# Occulow-Control.net
KiCad netlist of a schematic drawn in EAGLE
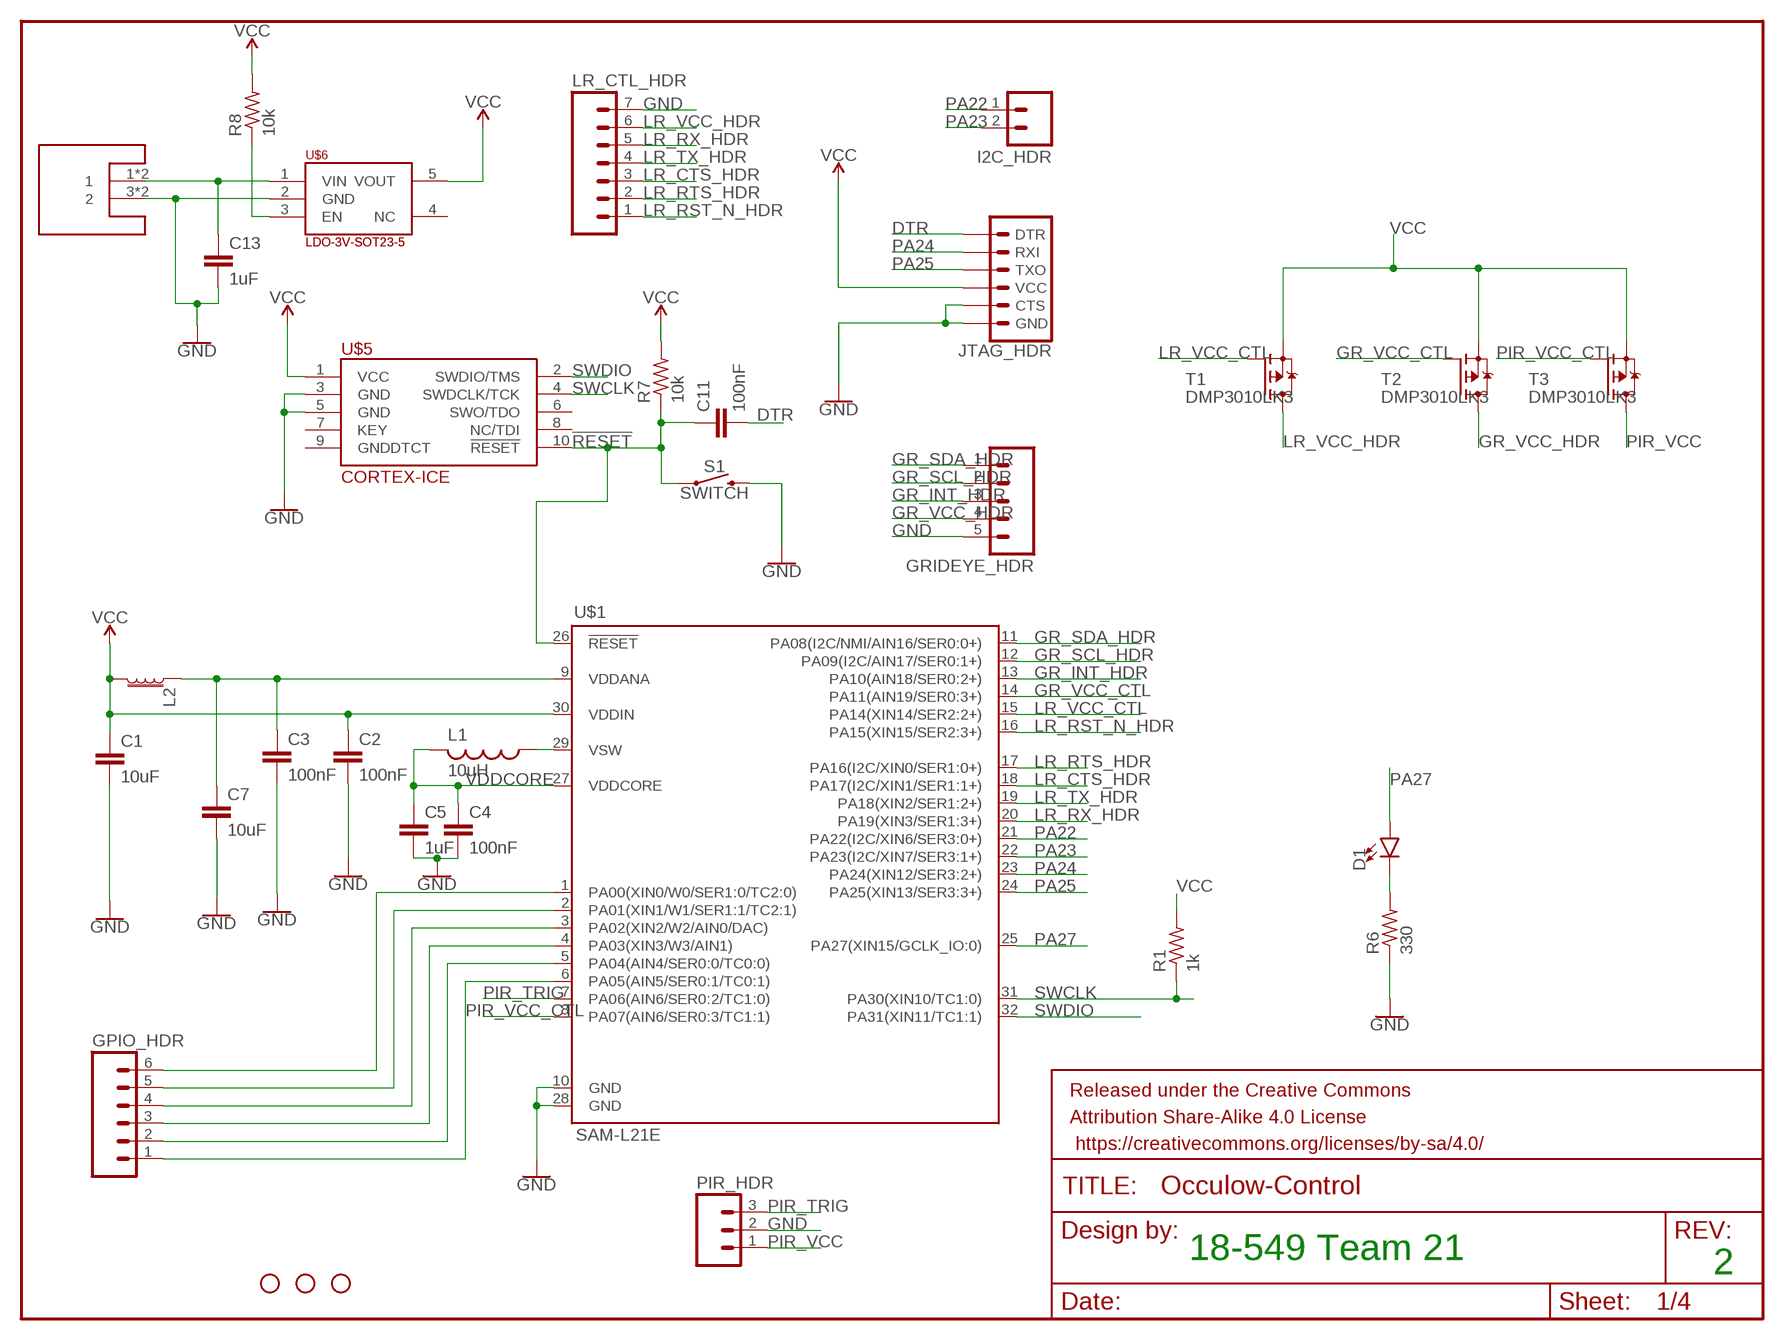
[diagram p0: schematic, sheet 1]
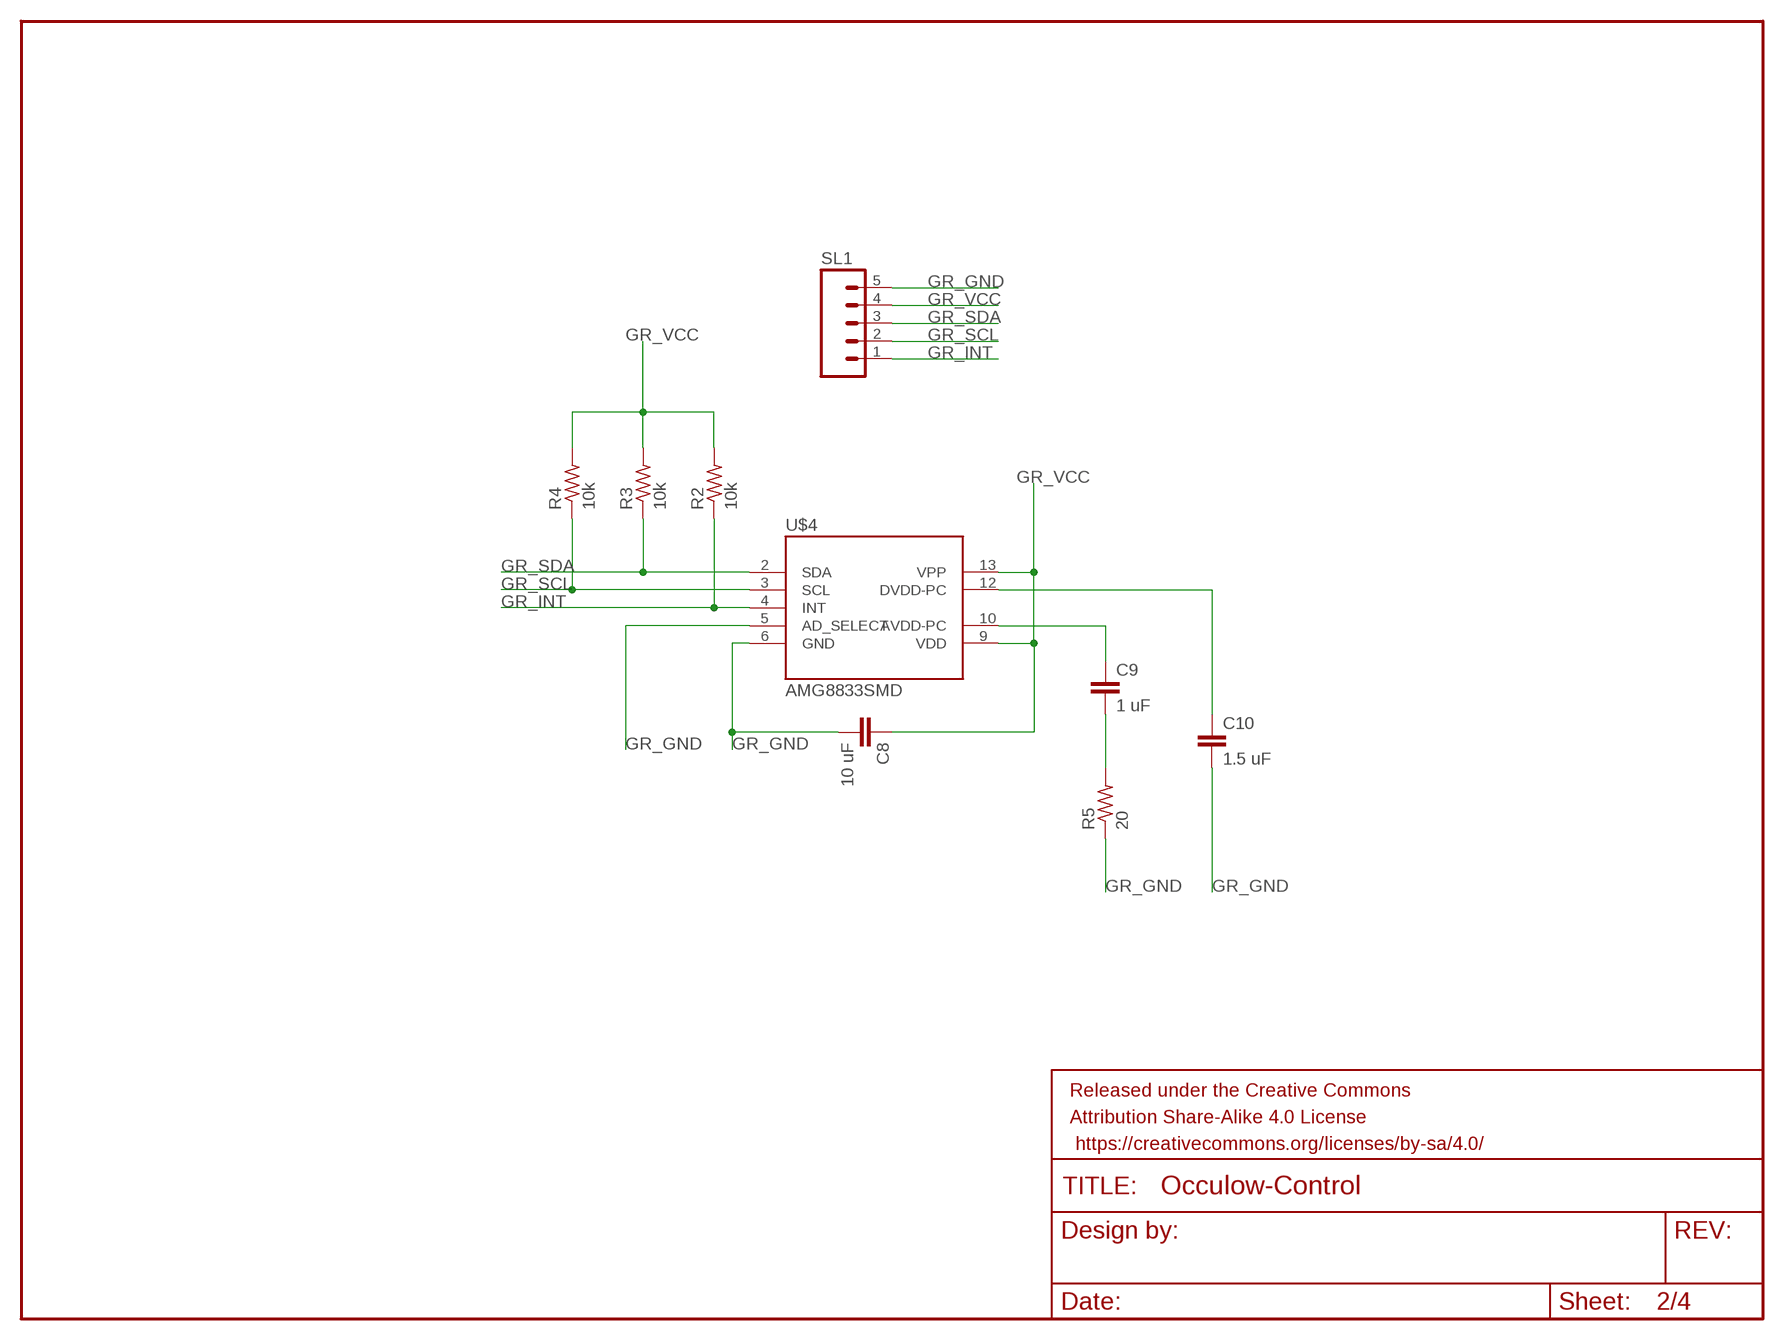
[diagram p1: schematic, sheet 2]
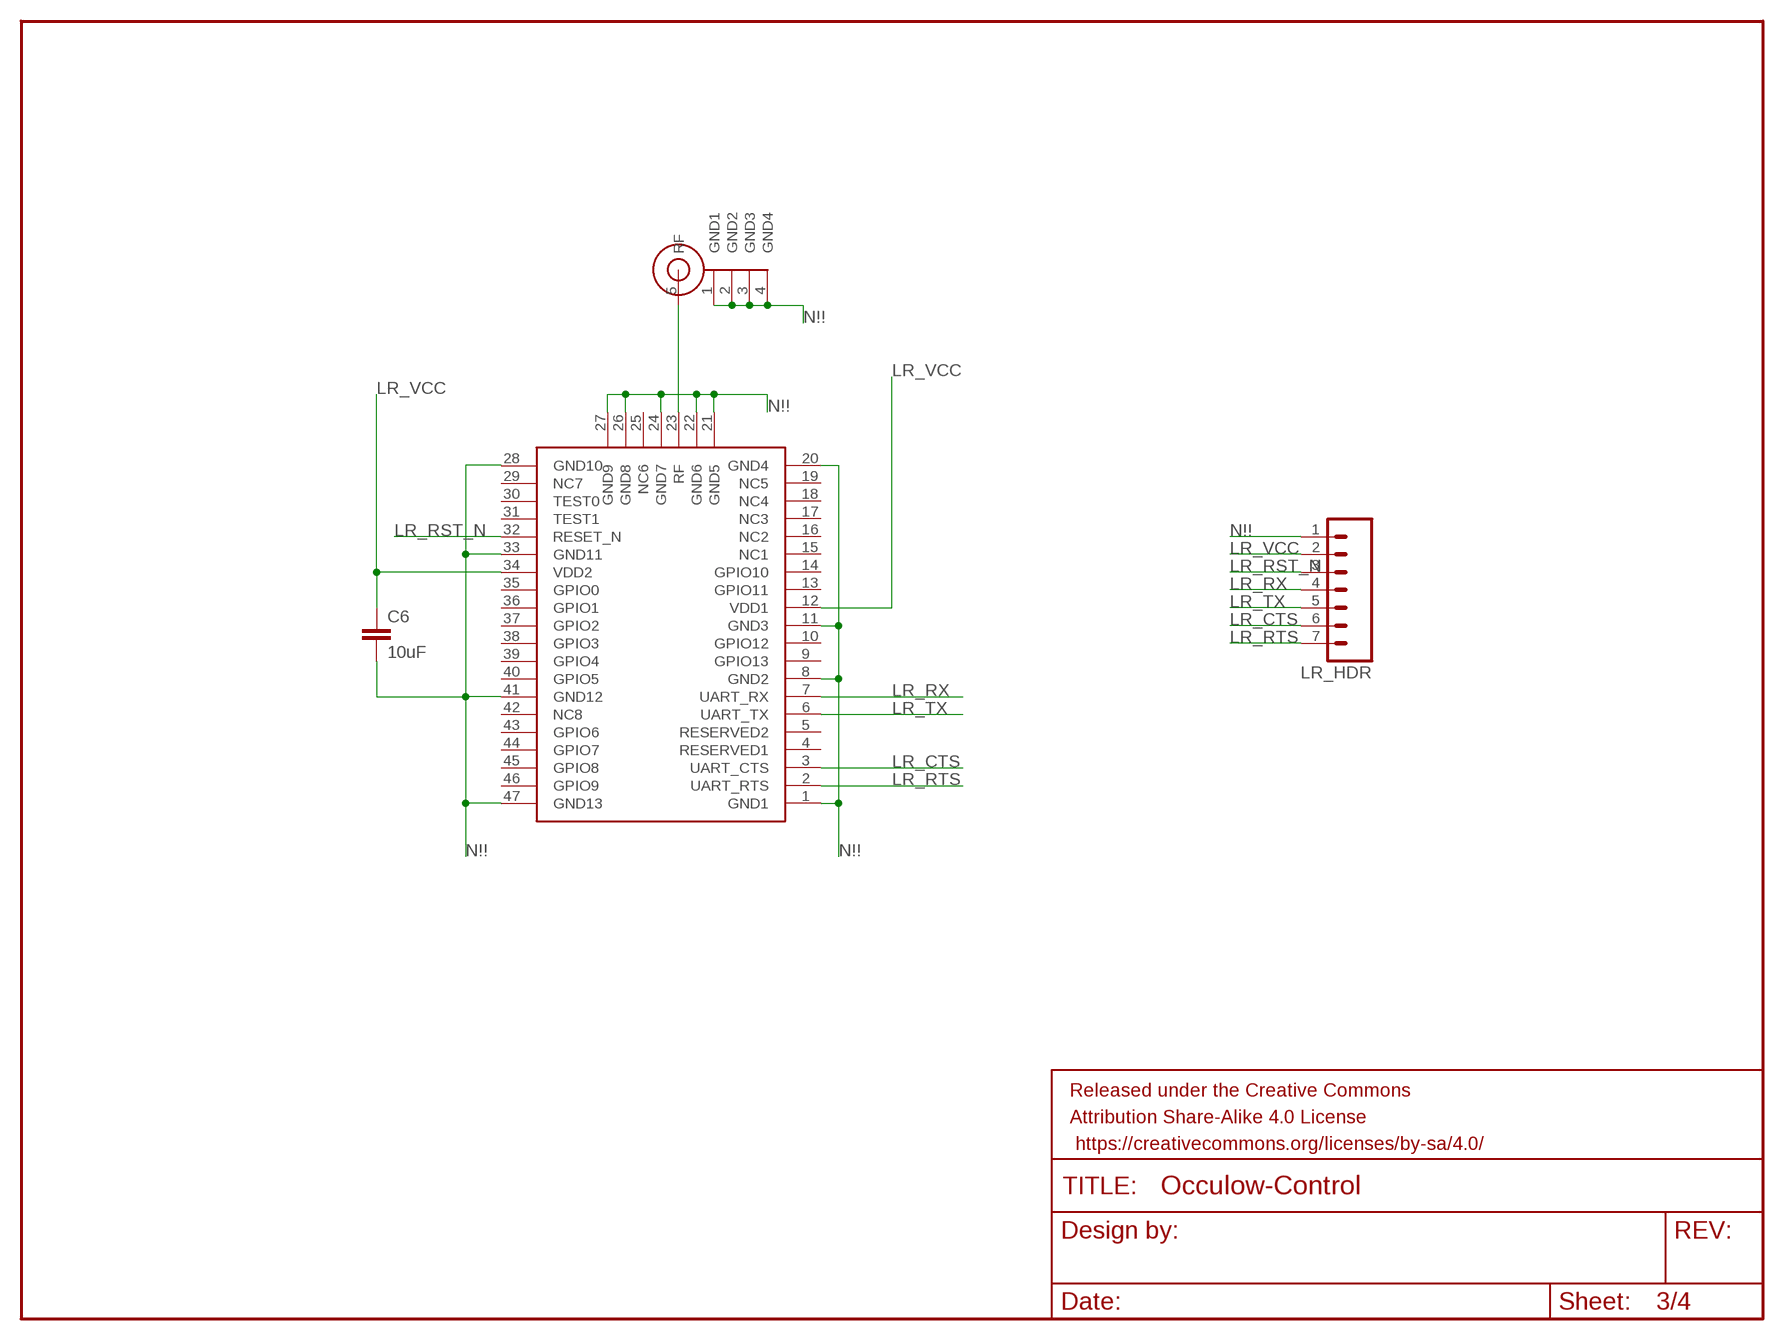
[diagram p2: schematic, sheet 3]

(export (version "E")
  (design (tool "Eeschema 10.0.6"))
  (components
    (comp (ref "C8")
      (value "10 uF")
      (footprint "eagle-import:C1206")
      (libsource (lib "eagle-import") (part "C-EUC1206"))
    )
    (comp (ref "C9")
      (value "1 uF")
      (footprint "eagle-import:C1206")
      (libsource (lib "eagle-import") (part "C-EUC1206"))
    )
    (comp (ref "C10")
      (value "1.5 uF")
      (footprint "eagle-import:C1206")
      (libsource (lib "eagle-import") (part "C-EUC1206"))
    )
    (comp (ref "FRAME2")
      (value "FRAME-LETTERNO_PACKAGE")
      (footprint "eagle-import:DUMMY")
      (fields (field (name "DESIGNER") "Nobody"))
      (libsource (lib "eagle-import") (part "FRAME-LETTERNO_PACKAGE"))
    )
    (comp (ref "R2")
      (value "10k")
      (footprint "eagle-import:R1206")
      (libsource (lib "eagle-import") (part "R-US_R1206"))
    )
    (comp (ref "R3")
      (value "10k")
      (footprint "eagle-import:R1206")
      (libsource (lib "eagle-import") (part "R-US_R1206"))
    )
    (comp (ref "R4")
      (value "10k")
      (footprint "eagle-import:R1206")
      (libsource (lib "eagle-import") (part "R-US_R1206"))
    )
    (comp (ref "R5")
      (value "20")
      (footprint "eagle-import:R1206")
      (libsource (lib "eagle-import") (part "R-US_R1206"))
    )
    (comp (ref "SL1")
      (value "M05")
      (footprint "eagle-import:05P")
      (libsource (lib "eagle-import") (part "M05"))
    )
    (comp (ref "U$4")
      (value "AMG8833SMD")
      (footprint "eagle-import:AMG8833")
      (libsource (lib "eagle-import") (part "AMG8833SMD"))
    )
    (comp (ref "C6")
      (value "10uF")
      (footprint "eagle-import:C1206")
      (libsource (lib "eagle-import") (part "C-EUC1206"))
    )
    (comp (ref "FRAME3")
      (value "FRAME-LETTERNO_PACKAGE")
      (footprint "eagle-import:DUMMY")
      (fields (field (name "DESIGNER") "Nobody"))
      (libsource (lib "eagle-import") (part "FRAME-LETTERNO_PACKAGE"))
    )
    (comp (ref "LR_HDR")
      (value "M07")
      (footprint "eagle-import:07P")
      (libsource (lib "eagle-import") (part "M07"))
    )
    (comp (ref "U$2")
      (value "RN2903")
      (footprint "eagle-import:RN2903")
      (libsource (lib "eagle-import") (part "RN2903"))
    )
    (comp (ref "U$3")
      (value "SMA-JACKFEMALE")
      (footprint "eagle-import:SMA-JACK")
      (libsource (lib "eagle-import") (part "SMA-JACKFEMALE"))
    )
    (comp (ref "C1")
      (value "10uF")
      (footprint "eagle-import:C1206")
      (libsource (lib "eagle-import") (part "C-EUC1206"))
    )
    (comp (ref "C2")
      (value "100nF")
      (footprint "eagle-import:C1206")
      (libsource (lib "eagle-import") (part "C-EUC1206"))
    )
    (comp (ref "C3")
      (value "100nF")
      (footprint "eagle-import:C1206")
      (libsource (lib "eagle-import") (part "C-EUC1206"))
    )
    (comp (ref "C4")
      (value "100nF")
      (footprint "eagle-import:C1206")
      (libsource (lib "eagle-import") (part "C-EUC1206"))
    )
    (comp (ref "C5")
      (value "1uF")
      (footprint "eagle-import:C1206")
      (libsource (lib "eagle-import") (part "C-EUC1206"))
    )
    (comp (ref "C7")
      (value "10uF")
      (footprint "eagle-import:C1206")
      (libsource (lib "eagle-import") (part "C-EUC1206"))
    )
    (comp (ref "C11")
      (value "100nF")
      (footprint "eagle-import:C1206")
      (libsource (lib "eagle-import") (part "C-EUC1206"))
    )
    (comp (ref "C13")
      (value "1uF")
      (footprint "eagle-import:C1206")
      (libsource (lib "eagle-import") (part "C-EUC1206"))
    )
    (comp (ref "D1")
      (value "LED1206")
      (footprint "eagle-import:LED-1206")
      (libsource (lib "eagle-import") (part "LED1206"))
    )
    (comp (ref "FRAME1")
      (value "FRAME-LETTERNO_PACKAGE")
      (footprint "eagle-import:DUMMY")
      (fields (field (name "DESIGNER") "Nobody"))
      (libsource (lib "eagle-import") (part "FRAME-LETTERNO_PACKAGE"))
    )
    (comp (ref "GPIO_HDR")
      (value "M06")
      (footprint "eagle-import:06P")
      (libsource (lib "eagle-import") (part "M06"))
    )
    (comp (ref "GRIDEYE_HDR")
      (value "M05")
      (footprint "eagle-import:05P")
      (libsource (lib "eagle-import") (part "M05"))
    )
    (comp (ref "H1")
      (value "STAND-OFF")
      (footprint "eagle-import:STAND-OFF")
      (libsource (lib "eagle-import") (part "STAND-OFF"))
    )
    (comp (ref "H2")
      (value "STAND-OFF")
      (footprint "eagle-import:STAND-OFF")
      (libsource (lib "eagle-import") (part "STAND-OFF"))
    )
    (comp (ref "H3")
      (value "STAND-OFF")
      (footprint "eagle-import:STAND-OFF")
      (libsource (lib "eagle-import") (part "STAND-OFF"))
    )
    (comp (ref "I2C_HDR")
      (value "M02")
      (footprint "eagle-import:02P")
      (libsource (lib "eagle-import") (part "M02"))
    )
    (comp (ref "JTAG_HDR")
      (value "6_PIN_SERIAL_TARGET")
      (footprint "eagle-import:1X06")
      (libsource (lib "eagle-import") (part "6_PIN_SERIAL_TARGET"))
    )
    (comp (ref "L1")
      (value "10uH")
      (footprint "eagle-import:L3225M")
      (libsource (lib "eagle-import") (part "L-USL3225M"))
    )
    (comp (ref "L2")
      (value "FERRITE_BEAD-0603")
      (footprint "eagle-import:0603")
      (libsource (lib "eagle-import") (part "FERRITE_BEAD-0603"))
    )
    (comp (ref "LR_CTL_HDR")
      (value "M07")
      (footprint "eagle-import:07P")
      (libsource (lib "eagle-import") (part "M07"))
    )
    (comp (ref "PIR_HDR")
      (value "M03")
      (footprint "eagle-import:03P")
      (libsource (lib "eagle-import") (part "M03"))
    )
    (comp (ref "R1")
      (value "1k")
      (footprint "eagle-import:R1206")
      (libsource (lib "eagle-import") (part "R-US_R1206"))
    )
    (comp (ref "R6")
      (value "330")
      (footprint "eagle-import:R1206")
      (libsource (lib "eagle-import") (part "R-US_R1206"))
    )
    (comp (ref "R7")
      (value "10k")
      (footprint "eagle-import:R1206")
      (libsource (lib "eagle-import") (part "R-US_R1206"))
    )
    (comp (ref "R8")
      (value "10k")
      (footprint "eagle-import:R1206")
      (libsource (lib "eagle-import") (part "R-US_R1206"))
    )
    (comp (ref "S1")
      (value "SWITCH")
      (footprint "eagle-import:TACTILE_SWITCH_SMD_5.2MM")
      (libsource (lib "eagle-import") (part "MOMENTARY-SWITCH-SPST-SMD-5.2-REDUNDANT"))
    )
    (comp (ref "T1")
      (value "DMP3010LK3")
      (footprint "eagle-import:TO252")
      (libsource (lib "eagle-import") (part "SPD30P06PTO252"))
    )
    (comp (ref "T2")
      (value "DMP3010LK3")
      (footprint "eagle-import:TO252")
      (libsource (lib "eagle-import") (part "SPD30P06PTO252"))
    )
    (comp (ref "T3")
      (value "DMP3010LK3")
      (footprint "eagle-import:TO252")
      (libsource (lib "eagle-import") (part "SPD30P06PTO252"))
    )
    (comp (ref "U$1")
      (value "SAM-L21E")
      (footprint "eagle-import:TQFP32")
      (libsource (lib "eagle-import") (part "SAM-L21E"))
    )
    (comp (ref "U$5")
      (value "CORTEX-ICE")
      (footprint "eagle-import:2X5-1.27MM")
      (libsource (lib "eagle-import") (part "CORTEX-ICE"))
    )
    (comp (ref "U$6")
      (value "LDO-3V-SOT23-5")
      (footprint "eagle-import:SOT23-5L")
      (libsource (lib "eagle-import") (part "LDO-3V-SOT23-5"))
    )
    (comp (ref "U$7")
      (value "MINI-LITE-TRAP")
      (footprint "eagle-import:MINI-LITE-TRAP")
      (libsource (lib "eagle-import") (part "MINI-LITE-TRAP"))
    )
  )
  (nets
    (net (code "1") (name "DTR") (class "Default")
      (node (ref "C11") (pin "2") (pinfunction "2_2") (pintype "passive"))
      (node (ref "JTAG_HDR") (pin "1") (pinfunction "DTR_1") (pintype "passive"))
    )
    (net (code "2") (name "GND") (class "Default")
      (node (ref "C1") (pin "2") (pinfunction "2_2") (pintype "passive"))
      (node (ref "C13") (pin "2") (pinfunction "2_2") (pintype "passive"))
      (node (ref "C2") (pin "2") (pinfunction "2_2") (pintype "passive"))
      (node (ref "C3") (pin "2") (pinfunction "2_2") (pintype "passive"))
      (node (ref "C4") (pin "2") (pinfunction "2_2") (pintype "passive"))
      (node (ref "C5") (pin "2") (pinfunction "2_2") (pintype "passive"))
      (node (ref "C7") (pin "2") (pinfunction "2_2") (pintype "passive"))
      (node (ref "GRIDEYE_HDR") (pin "5") (pinfunction "5_5") (pintype "passive"))
      (node (ref "JTAG_HDR") (pin "5") (pinfunction "CTS_5") (pintype "passive"))
      (node (ref "JTAG_HDR") (pin "6") (pinfunction "GND_6") (pintype "passive"))
      (node (ref "LR_CTL_HDR") (pin "7") (pinfunction "7_7") (pintype "passive"))
      (node (ref "PIR_HDR") (pin "2") (pinfunction "2_2") (pintype "passive"))
      (node (ref "R6") (pin "1") (pinfunction "1_1") (pintype "passive"))
      (node (ref "S1") (pin "3") (pinfunction "2_3") (pintype "passive"))
      (node (ref "S1") (pin "4") (pinfunction "2_4") (pintype "passive"))
      (node (ref "U$1") (pin "10") (pinfunction "GND_10") (pintype "bidirectional"))
      (node (ref "U$1") (pin "28") (pinfunction "GND_28") (pintype "bidirectional"))
      (node (ref "U$5") (pin "3") (pinfunction "GND_3") (pintype "bidirectional"))
      (node (ref "U$5") (pin "5") (pinfunction "GND_5") (pintype "bidirectional"))
      (node (ref "U$6") (pin "2") (pinfunction "GND_2") (pintype "bidirectional"))
      (node (ref "U$7") (pin "3") (pinfunction "2_3") (pintype "bidirectional"))
      (node (ref "U$7") (pin "4") (pinfunction "2_4") (pintype "bidirectional"))
    )
    (net (code "3") (name "GR_GND") (class "Default")
      (node (ref "C10") (pin "2") (pinfunction "2_2") (pintype "passive"))
      (node (ref "C8") (pin "2") (pinfunction "2_2") (pintype "passive"))
      (node (ref "R5") (pin "1") (pinfunction "1_1") (pintype "passive"))
      (node (ref "SL1") (pin "5") (pinfunction "5_5") (pintype "passive"))
      (node (ref "U$4") (pin "5") (pinfunction "AD_SELECT_5") (pintype "bidirectional"))
      (node (ref "U$4") (pin "6") (pinfunction "GND_6") (pintype "bidirectional"))
    )
    (net (code "4") (name "GR_INT") (class "Default")
      (node (ref "R2") (pin "1") (pinfunction "1_1") (pintype "passive"))
      (node (ref "SL1") (pin "1") (pinfunction "1_1") (pintype "passive"))
      (node (ref "U$4") (pin "4") (pinfunction "INT_4") (pintype "bidirectional"))
    )
    (net (code "5") (name "GR_INT_HDR") (class "Default")
      (node (ref "GRIDEYE_HDR") (pin "3") (pinfunction "3_3") (pintype "passive"))
      (node (ref "U$1") (pin "13") (pinfunction "PA10(AIN18/SER0:2+)_13") (pintype "bidirectional"))
    )
    (net (code "6") (name "GR_SCL") (class "Default")
      (node (ref "R4") (pin "1") (pinfunction "1_1") (pintype "passive"))
      (node (ref "SL1") (pin "2") (pinfunction "2_2") (pintype "passive"))
      (node (ref "U$4") (pin "3") (pinfunction "SCL_3") (pintype "bidirectional"))
    )
    (net (code "7") (name "GR_SCL_HDR") (class "Default")
      (node (ref "GRIDEYE_HDR") (pin "2") (pinfunction "2_2") (pintype "passive"))
      (node (ref "U$1") (pin "12") (pinfunction "PA09(I2C/AIN17/SER0:1+)_12") (pintype "bidirectional"))
    )
    (net (code "8") (name "GR_SDA") (class "Default")
      (node (ref "R3") (pin "1") (pinfunction "1_1") (pintype "passive"))
      (node (ref "SL1") (pin "3") (pinfunction "3_3") (pintype "passive"))
      (node (ref "U$4") (pin "2") (pinfunction "SDA_2") (pintype "bidirectional"))
    )
    (net (code "9") (name "GR_SDA_HDR") (class "Default")
      (node (ref "GRIDEYE_HDR") (pin "1") (pinfunction "1_1") (pintype "passive"))
      (node (ref "U$1") (pin "11") (pinfunction "PA08(I2C/NMI/AIN16/SER0:0+)_11") (pintype "bidirectional"))
    )
    (net (code "10") (name "GR_VCC") (class "Default")
      (node (ref "C8") (pin "1") (pinfunction "1_1") (pintype "passive"))
      (node (ref "R2") (pin "2") (pinfunction "2_2") (pintype "passive"))
      (node (ref "R3") (pin "2") (pinfunction "2_2") (pintype "passive"))
      (node (ref "R4") (pin "2") (pinfunction "2_2") (pintype "passive"))
      (node (ref "SL1") (pin "4") (pinfunction "4_4") (pintype "passive"))
      (node (ref "U$4") (pin "13") (pinfunction "VPP_13") (pintype "bidirectional"))
      (node (ref "U$4") (pin "9") (pinfunction "VDD_9") (pintype "bidirectional"))
    )
    (net (code "11") (name "GR_VCC_CTL") (class "Default")
      (node (ref "T2") (pin "1") (pinfunction "G_1") (pintype "passive"))
      (node (ref "U$1") (pin "14") (pinfunction "PA11(AIN19/SER0:3+)_14") (pintype "bidirectional"))
    )
    (net (code "12") (name "GR_VCC_HDR") (class "Default")
      (node (ref "GRIDEYE_HDR") (pin "4") (pinfunction "4_4") (pintype "passive"))
      (node (ref "T2") (pin "3") (pinfunction "D_3") (pintype "passive"))
    )
    (net (code "13") (name "LR_CTS") (class "Default")
      (node (ref "LR_HDR") (pin "6") (pinfunction "6_6") (pintype "passive"))
      (node (ref "U$2") (pin "3") (pinfunction "UART_CTS_3") (pintype "bidirectional"))
    )
    (net (code "14") (name "LR_CTS_HDR") (class "Default")
      (node (ref "LR_CTL_HDR") (pin "3") (pinfunction "3_3") (pintype "passive"))
      (node (ref "U$1") (pin "18") (pinfunction "PA17(I2C/XIN1/SER1:1+)_18") (pintype "bidirectional"))
    )
    (net (code "15") (name "LR_RST_N") (class "Default")
      (node (ref "LR_HDR") (pin "3") (pinfunction "3_3") (pintype "passive"))
      (node (ref "U$2") (pin "32") (pinfunction "RESET_N_32") (pintype "bidirectional"))
    )
    (net (code "16") (name "LR_RST_N_HDR") (class "Default")
      (node (ref "LR_CTL_HDR") (pin "1") (pinfunction "1_1") (pintype "passive"))
      (node (ref "U$1") (pin "16") (pinfunction "PA15(XIN15/SER2:3+)_16") (pintype "bidirectional"))
    )
    (net (code "17") (name "LR_RTS") (class "Default")
      (node (ref "LR_HDR") (pin "7") (pinfunction "7_7") (pintype "passive"))
      (node (ref "U$2") (pin "2") (pinfunction "UART_RTS_2") (pintype "bidirectional"))
    )
    (net (code "18") (name "LR_RTS_HDR") (class "Default")
      (node (ref "LR_CTL_HDR") (pin "2") (pinfunction "2_2") (pintype "passive"))
      (node (ref "U$1") (pin "17") (pinfunction "PA16(I2C/XIN0/SER1:0+)_17") (pintype "bidirectional"))
    )
    (net (code "19") (name "LR_RX") (class "Default")
      (node (ref "LR_HDR") (pin "4") (pinfunction "4_4") (pintype "passive"))
      (node (ref "U$2") (pin "7") (pinfunction "UART_RX_7") (pintype "bidirectional"))
    )
    (net (code "20") (name "LR_RX_HDR") (class "Default")
      (node (ref "LR_CTL_HDR") (pin "5") (pinfunction "5_5") (pintype "passive"))
      (node (ref "U$1") (pin "20") (pinfunction "PA19(XIN3/SER1:3+)_20") (pintype "bidirectional"))
    )
    (net (code "21") (name "LR_TX") (class "Default")
      (node (ref "LR_HDR") (pin "5") (pinfunction "5_5") (pintype "passive"))
      (node (ref "U$2") (pin "6") (pinfunction "UART_TX_6") (pintype "bidirectional"))
    )
    (net (code "22") (name "LR_TX_HDR") (class "Default")
      (node (ref "LR_CTL_HDR") (pin "4") (pinfunction "4_4") (pintype "passive"))
      (node (ref "U$1") (pin "19") (pinfunction "PA18(XIN2/SER1:2+)_19") (pintype "bidirectional"))
    )
    (net (code "23") (name "LR_VCC") (class "Default")
      (node (ref "C6") (pin "1") (pinfunction "1_1") (pintype "passive"))
      (node (ref "LR_HDR") (pin "2") (pinfunction "2_2") (pintype "passive"))
      (node (ref "U$2") (pin "12") (pinfunction "VDD1_12") (pintype "bidirectional"))
      (node (ref "U$2") (pin "34") (pinfunction "VDD2_34") (pintype "bidirectional"))
    )
    (net (code "24") (name "LR_VCC_CTL") (class "Default")
      (node (ref "T1") (pin "1") (pinfunction "G_1") (pintype "passive"))
      (node (ref "U$1") (pin "15") (pinfunction "PA14(XIN14/SER2:2+)_15") (pintype "bidirectional"))
    )
    (net (code "25") (name "LR_VCC_HDR") (class "Default")
      (node (ref "LR_CTL_HDR") (pin "6") (pinfunction "6_6") (pintype "passive"))
      (node (ref "T1") (pin "3") (pinfunction "D_3") (pintype "passive"))
    )
    (net (code "26") (name "Net-(C9-Pad2)") (class "Default")
      (node (ref "C9") (pin "2") (pinfunction "2_2") (pintype "passive"))
      (node (ref "R5") (pin "2") (pinfunction "2_2") (pintype "passive"))
    )
    (net (code "27") (name "Net-(D1-PadC)") (class "Default")
      (node (ref "D1") (pin "C") (pinfunction "C_C") (pintype "passive"))
      (node (ref "R6") (pin "2") (pinfunction "2_2") (pintype "passive"))
    )
    (net (code "28") (name "Net-(U$1-PA00(XIN0{slash}W0{slash}SER1:0{slash}TC2:0))") (class "Default")
      (node (ref "GPIO_HDR") (pin "6") (pinfunction "6_6") (pintype "passive"))
      (node (ref "U$1") (pin "1") (pinfunction "PA00(XIN0/W0/SER1:0/TC2:0)_1") (pintype "bidirectional"))
    )
    (net (code "29") (name "Net-(U$1-PA01(XIN1{slash}W1{slash}SER1:1{slash}TC2:1))") (class "Default")
      (node (ref "GPIO_HDR") (pin "5") (pinfunction "5_5") (pintype "passive"))
      (node (ref "U$1") (pin "2") (pinfunction "PA01(XIN1/W1/SER1:1/TC2:1)_2") (pintype "bidirectional"))
    )
    (net (code "30") (name "Net-(U$1-PA02(XIN2{slash}W2{slash}AIN0{slash}DAC))") (class "Default")
      (node (ref "GPIO_HDR") (pin "4") (pinfunction "4_4") (pintype "passive"))
      (node (ref "U$1") (pin "3") (pinfunction "PA02(XIN2/W2/AIN0/DAC)_3") (pintype "bidirectional"))
    )
    (net (code "31") (name "Net-(U$1-PA03(XIN3{slash}W3{slash}AIN1))") (class "Default")
      (node (ref "GPIO_HDR") (pin "3") (pinfunction "3_3") (pintype "passive"))
      (node (ref "U$1") (pin "4") (pinfunction "PA03(XIN3/W3/AIN1)_4") (pintype "bidirectional"))
    )
    (net (code "32") (name "Net-(U$1-PA04(AIN4{slash}SER0:0{slash}TC0:0))") (class "Default")
      (node (ref "GPIO_HDR") (pin "2") (pinfunction "2_2") (pintype "passive"))
      (node (ref "U$1") (pin "5") (pinfunction "PA04(AIN4/SER0:0/TC0:0)_5") (pintype "bidirectional"))
    )
    (net (code "33") (name "Net-(U$1-PA05(AIN5{slash}SER0:1{slash}TC0:1))") (class "Default")
      (node (ref "GPIO_HDR") (pin "1") (pinfunction "1_1") (pintype "passive"))
      (node (ref "U$1") (pin "6") (pinfunction "PA05(AIN5/SER0:1/TC0:1)_6") (pintype "bidirectional"))
    )
    (net (code "34") (name "Net-(U$1-VDDANA)") (class "Default")
      (node (ref "C3") (pin "1") (pinfunction "1_1") (pintype "passive"))
      (node (ref "C7") (pin "1") (pinfunction "1_1") (pintype "passive"))
      (node (ref "L2") (pin "1") (pinfunction "1_1") (pintype "passive"))
      (node (ref "U$1") (pin "9") (pinfunction "VDDANA_9") (pintype "bidirectional"))
    )
    (net (code "35") (name "Net-(U$1-VSW)") (class "Default")
      (node (ref "L1") (pin "1") (pinfunction "1_1") (pintype "passive"))
      (node (ref "U$1") (pin "29") (pinfunction "VSW_29") (pintype "bidirectional"))
    )
    (net (code "36") (name "Net-(U$2-RF)") (class "Default")
      (node (ref "U$2") (pin "23") (pinfunction "RF_23") (pintype "bidirectional"))
      (node (ref "U$3") (pin "5") (pinfunction "RF_5") (pintype "bidirectional"))
    )
    (net (code "37") (name "Net-(U$4-AVDD-PC)") (class "Default")
      (node (ref "C9") (pin "1") (pinfunction "1_1") (pintype "passive"))
      (node (ref "U$4") (pin "10") (pinfunction "AVDD-PC_10") (pintype "bidirectional"))
    )
    (net (code "38") (name "Net-(U$4-DVDD-PC)") (class "Default")
      (node (ref "C10") (pin "1") (pinfunction "1_1") (pintype "passive"))
      (node (ref "U$4") (pin "12") (pinfunction "DVDD-PC_12") (pintype "bidirectional"))
    )
    (net (code "39") (name "Net-(U$6-EN)") (class "Default")
      (node (ref "R8") (pin "1") (pinfunction "1_1") (pintype "passive"))
      (node (ref "U$6") (pin "3") (pinfunction "EN_3") (pintype "bidirectional"))
    )
    (net (code "40") (name "Net-(U$6-VIN)") (class "Default")
      (node (ref "C13") (pin "1") (pinfunction "1_1") (pintype "passive"))
      (node (ref "U$6") (pin "1") (pinfunction "VIN_1") (pintype "bidirectional"))
      (node (ref "U$7") (pin "1") (pinfunction "1_1") (pintype "bidirectional"))
      (node (ref "U$7") (pin "2") (pinfunction "1_2") (pintype "bidirectional"))
    )
    (net (code "41") (name "N~") (class "Default")
      (node (ref "C6") (pin "2") (pinfunction "2_2") (pintype "passive"))
      (node (ref "LR_HDR") (pin "1") (pinfunction "1_1") (pintype "passive"))
      (node (ref "U$2") (pin "1") (pinfunction "GND1_1") (pintype "bidirectional"))
      (node (ref "U$2") (pin "11") (pinfunction "GND3_11") (pintype "bidirectional"))
      (node (ref "U$2") (pin "20") (pinfunction "GND4_20") (pintype "bidirectional"))
      (node (ref "U$2") (pin "21") (pinfunction "GND5_21") (pintype "bidirectional"))
      (node (ref "U$2") (pin "22") (pinfunction "GND6_22") (pintype "bidirectional"))
      (node (ref "U$2") (pin "24") (pinfunction "GND7_24") (pintype "bidirectional"))
      (node (ref "U$2") (pin "26") (pinfunction "GND8_26") (pintype "bidirectional"))
      (node (ref "U$2") (pin "27") (pinfunction "GND9_27") (pintype "bidirectional"))
      (node (ref "U$2") (pin "28") (pinfunction "GND10_28") (pintype "bidirectional"))
      (node (ref "U$2") (pin "33") (pinfunction "GND11_33") (pintype "bidirectional"))
      (node (ref "U$2") (pin "41") (pinfunction "GND12_41") (pintype "bidirectional"))
      (node (ref "U$2") (pin "47") (pinfunction "GND13_47") (pintype "bidirectional"))
      (node (ref "U$2") (pin "8") (pinfunction "GND2_8") (pintype "bidirectional"))
      (node (ref "U$3") (pin "1") (pinfunction "GND1_1") (pintype "bidirectional"))
      (node (ref "U$3") (pin "2") (pinfunction "GND2_2") (pintype "bidirectional"))
      (node (ref "U$3") (pin "3") (pinfunction "GND3_3") (pintype "bidirectional"))
      (node (ref "U$3") (pin "4") (pinfunction "GND4_4") (pintype "bidirectional"))
    )
    (net (code "42") (name "PA22") (class "Default")
      (node (ref "I2C_HDR") (pin "1") (pinfunction "1_1") (pintype "passive"))
      (node (ref "U$1") (pin "21") (pinfunction "PA22(I2C/XIN6/SER3:0+)_21") (pintype "bidirectional"))
    )
    (net (code "43") (name "PA23") (class "Default")
      (node (ref "I2C_HDR") (pin "2") (pinfunction "2_2") (pintype "passive"))
      (node (ref "U$1") (pin "22") (pinfunction "PA23(I2C/XIN7/SER3:1+)_22") (pintype "bidirectional"))
    )
    (net (code "44") (name "PA24") (class "Default")
      (node (ref "JTAG_HDR") (pin "2") (pinfunction "RXI_2") (pintype "passive"))
      (node (ref "U$1") (pin "23") (pinfunction "PA24(XIN12/SER3:2+)_23") (pintype "bidirectional"))
    )
    (net (code "45") (name "PA25") (class "Default")
      (node (ref "JTAG_HDR") (pin "3") (pinfunction "TXO_3") (pintype "passive"))
      (node (ref "U$1") (pin "24") (pinfunction "PA25(XIN13/SER3:3+)_24") (pintype "bidirectional"))
    )
    (net (code "46") (name "PA27") (class "Default")
      (node (ref "D1") (pin "A") (pinfunction "A_A") (pintype "passive"))
      (node (ref "U$1") (pin "25") (pinfunction "PA27(XIN15/GCLK_IO:0)_25") (pintype "bidirectional"))
    )
    (net (code "47") (name "PIR_TRIG") (class "Default")
      (node (ref "PIR_HDR") (pin "3") (pinfunction "3_3") (pintype "passive"))
      (node (ref "U$1") (pin "7") (pinfunction "PA06(AIN6/SER0:2/TC1:0)_7") (pintype "bidirectional"))
    )
    (net (code "48") (name "PIR_VCC") (class "Default")
      (node (ref "PIR_HDR") (pin "1") (pinfunction "1_1") (pintype "passive"))
      (node (ref "T3") (pin "3") (pinfunction "D_3") (pintype "passive"))
    )
    (net (code "49") (name "PIR_VCC_CTL") (class "Default")
      (node (ref "T3") (pin "1") (pinfunction "G_1") (pintype "passive"))
      (node (ref "U$1") (pin "8") (pinfunction "PA07(AIN6/SER0:3/TC1:1)_8") (pintype "bidirectional"))
    )
    (net (code "50") (name "SWCLK") (class "Default")
      (node (ref "R1") (pin "1") (pinfunction "1_1") (pintype "passive"))
      (node (ref "U$1") (pin "31") (pinfunction "PA30(XIN10/TC1:0)_31") (pintype "bidirectional"))
      (node (ref "U$5") (pin "4") (pinfunction "SWDCLK/TCK_4") (pintype "bidirectional"))
    )
    (net (code "51") (name "SWDIO") (class "Default")
      (node (ref "U$1") (pin "32") (pinfunction "PA31(XIN11/TC1:1)_32") (pintype "bidirectional"))
      (node (ref "U$5") (pin "2") (pinfunction "SWDIO/TMS_2") (pintype "bidirectional"))
    )
    (net (code "52") (name "VCC") (class "Default")
      (node (ref "C1") (pin "1") (pinfunction "1_1") (pintype "passive"))
      (node (ref "C2") (pin "1") (pinfunction "1_1") (pintype "passive"))
      (node (ref "JTAG_HDR") (pin "4") (pinfunction "VCC_4") (pintype "passive"))
      (node (ref "L2") (pin "2") (pinfunction "2_2") (pintype "passive"))
      (node (ref "R1") (pin "2") (pinfunction "2_2") (pintype "passive"))
      (node (ref "R7") (pin "2") (pinfunction "2_2") (pintype "passive"))
      (node (ref "R8") (pin "2") (pinfunction "2_2") (pintype "passive"))
      (node (ref "T1") (pin "2") (pinfunction "S_2") (pintype "passive"))
      (node (ref "T2") (pin "2") (pinfunction "S_2") (pintype "passive"))
      (node (ref "T3") (pin "2") (pinfunction "S_2") (pintype "passive"))
      (node (ref "U$1") (pin "30") (pinfunction "VDDIN_30") (pintype "bidirectional"))
      (node (ref "U$5") (pin "1") (pinfunction "VCC_1") (pintype "bidirectional"))
      (node (ref "U$6") (pin "5") (pinfunction "VOUT_5") (pintype "bidirectional"))
    )
    (net (code "53") (name "VDDCORE") (class "Default")
      (node (ref "C4") (pin "1") (pinfunction "1_1") (pintype "passive"))
      (node (ref "C5") (pin "1") (pinfunction "1_1") (pintype "passive"))
      (node (ref "L1") (pin "2") (pinfunction "2_2") (pintype "passive"))
      (node (ref "U$1") (pin "27") (pinfunction "VDDCORE_27") (pintype "bidirectional"))
    )
    (net (code "54") (name "unconnected-(U$2-GPIO0-Pad35)") (class "Default")
      (node (ref "U$2") (pin "35") (pinfunction "GPIO0_35") (pintype "bidirectional"))
    )
    (net (code "55") (name "unconnected-(U$2-GPIO1-Pad36)") (class "Default")
      (node (ref "U$2") (pin "36") (pinfunction "GPIO1_36") (pintype "bidirectional"))
    )
    (net (code "56") (name "unconnected-(U$2-GPIO2-Pad37)") (class "Default")
      (node (ref "U$2") (pin "37") (pinfunction "GPIO2_37") (pintype "bidirectional"))
    )
    (net (code "57") (name "unconnected-(U$2-GPIO3-Pad38)") (class "Default")
      (node (ref "U$2") (pin "38") (pinfunction "GPIO3_38") (pintype "bidirectional"))
    )
    (net (code "58") (name "unconnected-(U$2-GPIO4-Pad39)") (class "Default")
      (node (ref "U$2") (pin "39") (pinfunction "GPIO4_39") (pintype "bidirectional"))
    )
    (net (code "59") (name "unconnected-(U$2-GPIO5-Pad40)") (class "Default")
      (node (ref "U$2") (pin "40") (pinfunction "GPIO5_40") (pintype "bidirectional"))
    )
    (net (code "60") (name "unconnected-(U$2-GPIO6-Pad43)") (class "Default")
      (node (ref "U$2") (pin "43") (pinfunction "GPIO6_43") (pintype "bidirectional"))
    )
    (net (code "61") (name "unconnected-(U$2-GPIO7-Pad44)") (class "Default")
      (node (ref "U$2") (pin "44") (pinfunction "GPIO7_44") (pintype "bidirectional"))
    )
    (net (code "62") (name "unconnected-(U$2-GPIO8-Pad45)") (class "Default")
      (node (ref "U$2") (pin "45") (pinfunction "GPIO8_45") (pintype "bidirectional"))
    )
    (net (code "63") (name "unconnected-(U$2-GPIO9-Pad46)") (class "Default")
      (node (ref "U$2") (pin "46") (pinfunction "GPIO9_46") (pintype "bidirectional"))
    )
    (net (code "64") (name "unconnected-(U$2-GPIO10-Pad14)") (class "Default")
      (node (ref "U$2") (pin "14") (pinfunction "GPIO10_14") (pintype "bidirectional"))
    )
    (net (code "65") (name "unconnected-(U$2-GPIO11-Pad13)") (class "Default")
      (node (ref "U$2") (pin "13") (pinfunction "GPIO11_13") (pintype "bidirectional"))
    )
    (net (code "66") (name "unconnected-(U$2-GPIO12-Pad10)") (class "Default")
      (node (ref "U$2") (pin "10") (pinfunction "GPIO12_10") (pintype "bidirectional"))
    )
    (net (code "67") (name "unconnected-(U$2-GPIO13-Pad9)") (class "Default")
      (node (ref "U$2") (pin "9") (pinfunction "GPIO13_9") (pintype "bidirectional"))
    )
    (net (code "68") (name "unconnected-(U$2-NC1-Pad15)") (class "Default")
      (node (ref "U$2") (pin "15") (pinfunction "NC1_15") (pintype "bidirectional"))
    )
    (net (code "69") (name "unconnected-(U$2-NC2-Pad16)") (class "Default")
      (node (ref "U$2") (pin "16") (pinfunction "NC2_16") (pintype "bidirectional"))
    )
    (net (code "70") (name "unconnected-(U$2-NC3-Pad17)") (class "Default")
      (node (ref "U$2") (pin "17") (pinfunction "NC3_17") (pintype "bidirectional"))
    )
    (net (code "71") (name "unconnected-(U$2-NC4-Pad18)") (class "Default")
      (node (ref "U$2") (pin "18") (pinfunction "NC4_18") (pintype "bidirectional"))
    )
    (net (code "72") (name "unconnected-(U$2-NC5-Pad19)") (class "Default")
      (node (ref "U$2") (pin "19") (pinfunction "NC5_19") (pintype "bidirectional"))
    )
    (net (code "73") (name "unconnected-(U$2-NC6-Pad25)") (class "Default")
      (node (ref "U$2") (pin "25") (pinfunction "NC6_25") (pintype "bidirectional"))
    )
    (net (code "74") (name "unconnected-(U$2-NC7-Pad29)") (class "Default")
      (node (ref "U$2") (pin "29") (pinfunction "NC7_29") (pintype "bidirectional"))
    )
    (net (code "75") (name "unconnected-(U$2-NC8-Pad42)") (class "Default")
      (node (ref "U$2") (pin "42") (pinfunction "NC8_42") (pintype "bidirectional"))
    )
    (net (code "76") (name "unconnected-(U$2-RESERVED1-Pad4)") (class "Default")
      (node (ref "U$2") (pin "4") (pinfunction "RESERVED1_4") (pintype "bidirectional"))
    )
    (net (code "77") (name "unconnected-(U$2-RESERVED2-Pad5)") (class "Default")
      (node (ref "U$2") (pin "5") (pinfunction "RESERVED2_5") (pintype "bidirectional"))
    )
    (net (code "78") (name "unconnected-(U$2-TEST0-Pad30)") (class "Default")
      (node (ref "U$2") (pin "30") (pinfunction "TEST0_30") (pintype "bidirectional"))
    )
    (net (code "79") (name "unconnected-(U$2-TEST1-Pad31)") (class "Default")
      (node (ref "U$2") (pin "31") (pinfunction "TEST1_31") (pintype "bidirectional"))
    )
    (net (code "80") (name "unconnected-(U$5-GNDDTCT-Pad9)") (class "Default")
      (node (ref "U$5") (pin "9") (pinfunction "GNDDTCT_9") (pintype "bidirectional"))
    )
    (net (code "81") (name "unconnected-(U$5-KEY-Pad7)") (class "Default")
      (node (ref "U$5") (pin "7") (pinfunction "KEY_7") (pintype "bidirectional"))
    )
    (net (code "82") (name "unconnected-(U$5-NC{slash}TDI-Pad8)") (class "Default")
      (node (ref "U$5") (pin "8") (pinfunction "NC/TDI_8") (pintype "bidirectional"))
    )
    (net (code "83") (name "unconnected-(U$5-SWO{slash}TDO-Pad6)") (class "Default")
      (node (ref "U$5") (pin "6") (pinfunction "SWO/TDO_6") (pintype "bidirectional"))
    )
    (net (code "84") (name "unconnected-(U$6-NC-Pad4)") (class "Default")
      (node (ref "U$6") (pin "4") (pinfunction "NC_4") (pintype "bidirectional"))
    )
    (net (code "85") (name "~{RESET}") (class "Default")
      (node (ref "C11") (pin "1") (pinfunction "1_1") (pintype "passive"))
      (node (ref "R7") (pin "1") (pinfunction "1_1") (pintype "passive"))
      (node (ref "S1") (pin "1") (pinfunction "1_1") (pintype "passive"))
      (node (ref "S1") (pin "2") (pinfunction "1_2") (pintype "passive"))
      (node (ref "U$1") (pin "26") (pinfunction "~{RESET}_26") (pintype "bidirectional"))
      (node (ref "U$5") (pin "10") (pinfunction "~{RESET}_10") (pintype "bidirectional"))
    )
  )
)
